# Mosfet.net
KiCad netlist of a schematic drawn in Altium Designer
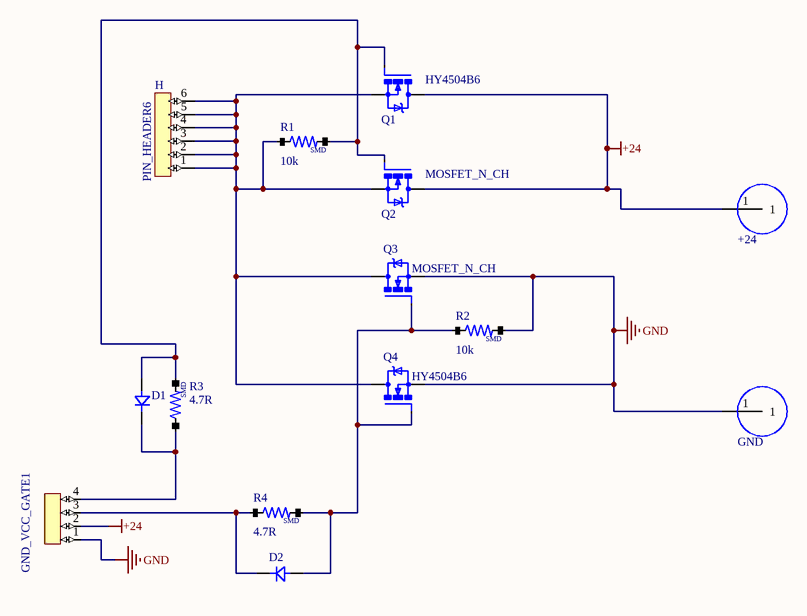
[diagram p0: Mosfet.SchDoc]

(export (version "E")
  (design (tool "Eeschema 10.0.6"))
  (components
    (comp (ref "+24") (value "PIN1") (footprint "PIN1") (libsource (lib "kave-eng-pro") (part "PIN1")))
    (comp (ref "D1")
      (value "~")
      (footprint "mini_melf")
      (libsource (lib "kave-eng-pro") (part "DIOD/RECTIFIERS"))
    )
    (comp (ref "D2")
      (value "~")
      (footprint "mini_melf")
      (libsource (lib "kave-eng-pro") (part "DIOD/RECTIFIERS"))
    )
    (comp (ref "GND") (value "PIN1") (footprint "PIN1") (libsource (lib "kave-eng-pro") (part "PIN1")))
    (comp (ref "GND_VCC_GATE1")
      (value "CONECTOR/XH/4PIN")
      (footprint "CONECTOR/XH/4PIN")
      (libsource (lib "kave-eng-pro") (part "CONECTOR/XH/4PIN"))
    )
    (comp (ref "H")
      (value "PIN_HEADER6")
      (footprint "pin_header_6pin")
      (libsource (lib "kave-eng-pro") (part "PIN_HEADER6"))
    )
    (comp (ref "Q1") (value "HY4504B6") (footprint "TO-263-6L") (libsource (lib "") (part "MOSFET_N_CH_1")))
    (comp (ref "Q2")
      (value "MOSFET_N_CH")
      (footprint "HYG025N06LS1C2")
      (libsource (lib "") (part "MOSFET_N_CH_1"))
    )
    (comp (ref "Q3")
      (value "MOSFET_N_CH")
      (footprint "TO-263-6L")
      (libsource (lib "kave-eng-pro") (part "MOSFET_N_CH"))
    )
    (comp (ref "Q4")
      (value "HY4504B6")
      (footprint "HYG025N06LS1C2")
      (libsource (lib "kave-eng-pro") (part "MOSFET_N_CH"))
    )
    (comp (ref "R1") (value "10k") (footprint "RES/0603") (libsource (lib "kave-eng-pro") (part "RES/SMD")))
    (comp (ref "R2") (value "10k") (footprint "RES/0603") (libsource (lib "kave-eng-pro") (part "RES/SMD")))
    (comp (ref "R3") (value "4.7R") (footprint "RES/0805") (libsource (lib "") (part "RES/SMD_1")))
    (comp (ref "R4") (value "4.7R") (footprint "RES/0805") (libsource (lib "kave-eng-pro") (part "RES/SMD")))
  )
  (nets
    (net (code "1") (name "+24") (class "Default")
      (node (ref "+24") (pin "1") (pinfunction "1_1") (pintype "passive"))
      (node (ref "GND_VCC_GATE1") (pin "2") (pintype "bidirectional"))
      (node (ref "Q1") (pin "2") (pinfunction "D_2") (pintype "passive"))
      (node (ref "Q2") (pin "2") (pinfunction "D_2") (pintype "passive"))
    )
    (net (code "2") (name "GND") (class "Default")
      (node (ref "GND") (pin "1") (pinfunction "1_1") (pintype "passive"))
      (node (ref "GND_VCC_GATE1") (pin "1") (pintype "bidirectional"))
      (node (ref "Q3") (pin "3") (pinfunction "s_3") (pintype "passive"))
      (node (ref "Q4") (pin "3") (pinfunction "s_3") (pintype "passive"))
      (node (ref "R2") (pin "2") (pinfunction "2_2") (pintype "passive"))
    )
    (net (code "3") (name "Net-(D1-PadK)") (class "Default")
      (node (ref "D1") (pin "K") (pintype "passive"))
      (node (ref "GND_VCC_GATE1") (pin "4") (pintype "bidirectional"))
      (node (ref "R3") (pin "1") (pinfunction "1_1") (pintype "passive"))
    )
    (net (code "4") (name "Net-(D2-PadK)") (class "Default")
      (node (ref "D2") (pin "K") (pintype "passive"))
      (node (ref "GND_VCC_GATE1") (pin "3") (pintype "bidirectional"))
      (node (ref "R4") (pin "1") (pinfunction "1_1") (pintype "passive"))
    )
    (net (code "5") (name "Net-(Q1-G)") (class "Default")
      (node (ref "D1") (pin "A") (pintype "passive"))
      (node (ref "Q1") (pin "1") (pinfunction "G_1") (pintype "passive"))
      (node (ref "Q2") (pin "1") (pinfunction "G_1") (pintype "passive"))
      (node (ref "R1") (pin "2") (pinfunction "2_2") (pintype "passive"))
      (node (ref "R3") (pin "2") (pinfunction "2_2") (pintype "passive"))
    )
    (net (code "6") (name "Net-(Q1-s)") (class "Default")
      (node (ref "H") (pin "1") (pintype "bidirectional"))
      (node (ref "H") (pin "2") (pintype "bidirectional"))
      (node (ref "H") (pin "3") (pintype "bidirectional"))
      (node (ref "H") (pin "4") (pintype "bidirectional"))
      (node (ref "H") (pin "5") (pintype "bidirectional"))
      (node (ref "H") (pin "6") (pintype "bidirectional"))
      (node (ref "Q1") (pin "3") (pinfunction "s_3") (pintype "passive"))
      (node (ref "Q2") (pin "3") (pinfunction "s_3") (pintype "passive"))
      (node (ref "Q3") (pin "2") (pinfunction "D_2") (pintype "passive"))
      (node (ref "Q4") (pin "2") (pinfunction "D_2") (pintype "passive"))
      (node (ref "R1") (pin "1") (pinfunction "1_1") (pintype "passive"))
    )
    (net (code "7") (name "Net-(Q3-G)") (class "Default")
      (node (ref "D2") (pin "A") (pintype "passive"))
      (node (ref "Q3") (pin "1") (pinfunction "G_1") (pintype "passive"))
      (node (ref "Q4") (pin "1") (pinfunction "G_1") (pintype "passive"))
      (node (ref "R2") (pin "1") (pinfunction "1_1") (pintype "passive"))
      (node (ref "R4") (pin "2") (pinfunction "2_2") (pintype "passive"))
    )
  )
)
